# Driver.net
KiCad netlist of a schematic drawn in EAGLE
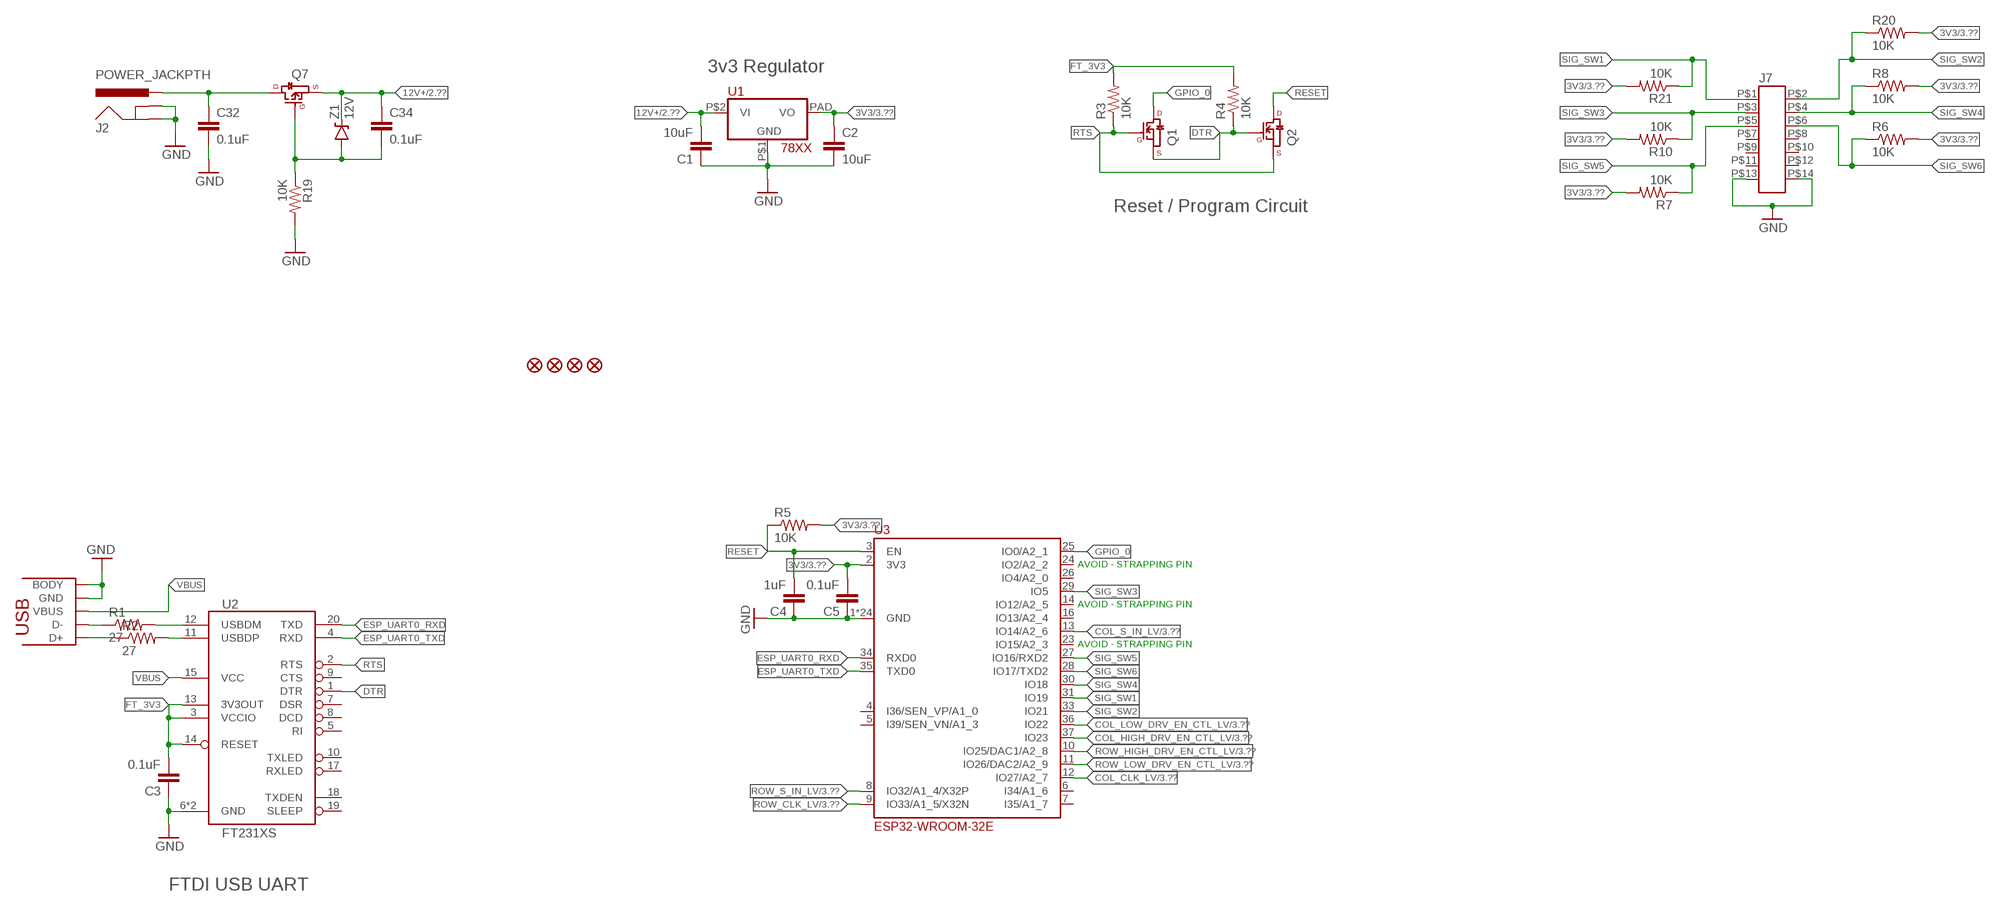
[diagram p0: schematic, sheet 1]
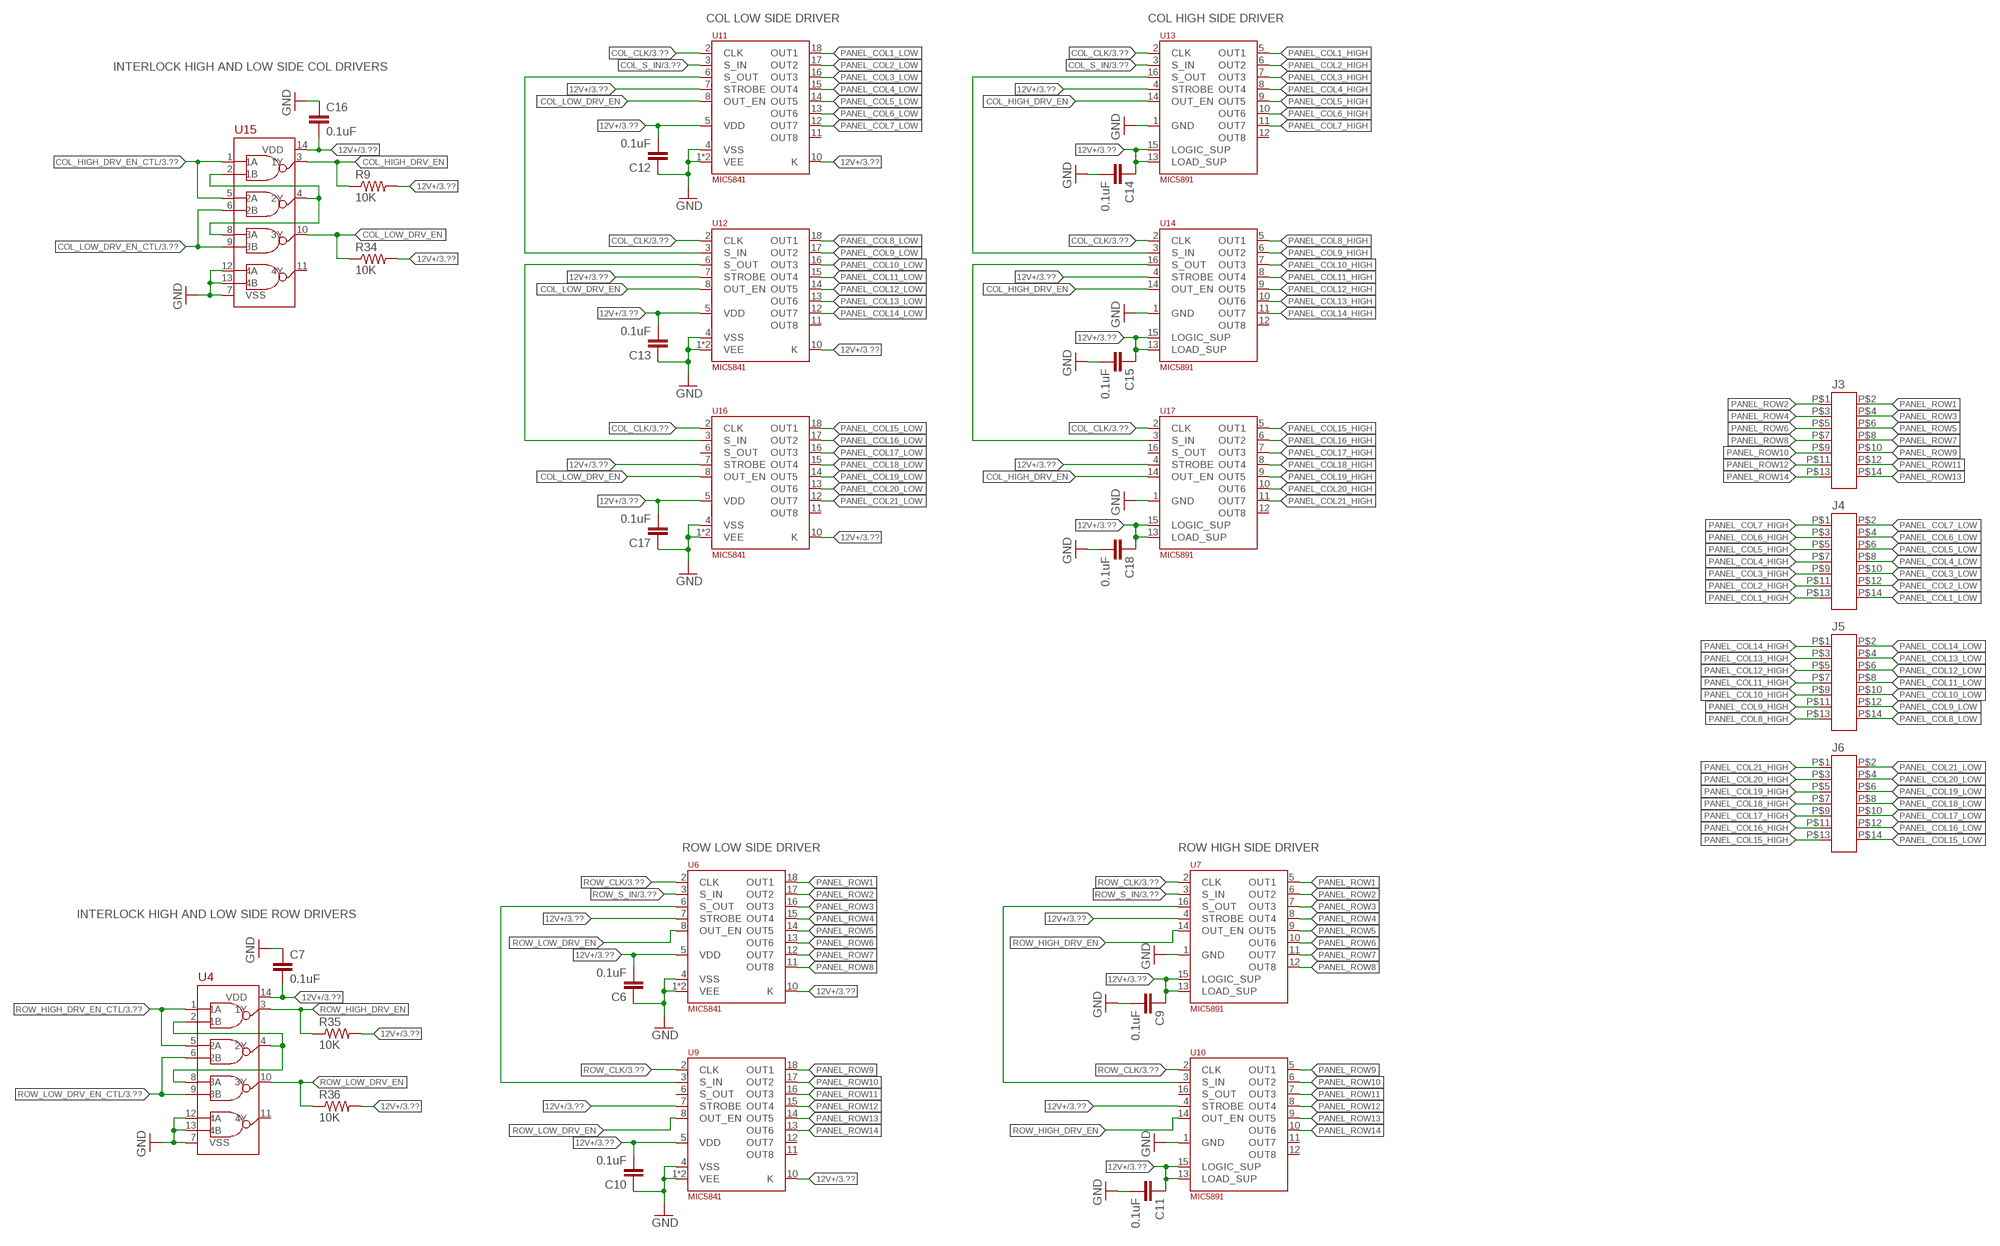
[diagram p1: schematic, sheet 2]
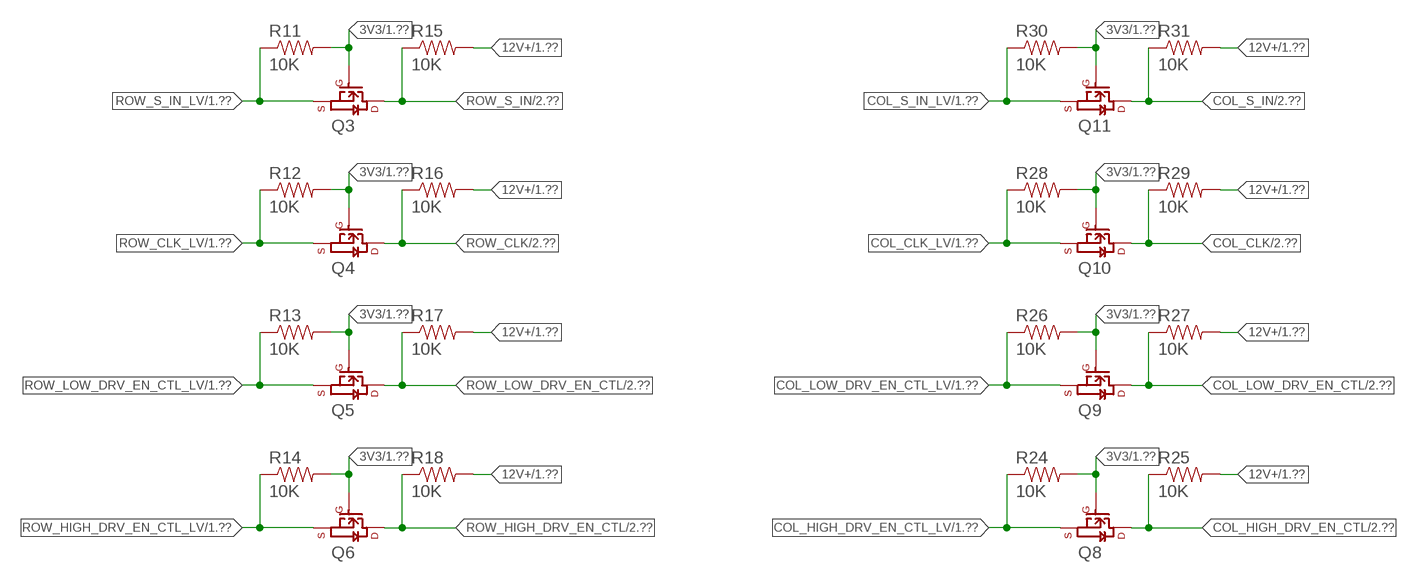
[diagram p2: schematic, sheet 3]

(export (version "E")
  (design (tool "Eeschema 10.0.6"))
  (components
    (comp (ref "Q3")
      (value "MOSFET_N_CHANNELFDV305N")
      (footprint "eagle-import:SOT-23")
      (libsource (lib "eagle-import") (part "MOSFET_N_CHANNELFDV305N"))
    )
    (comp (ref "Q4")
      (value "MOSFET_N_CHANNELFDV305N")
      (footprint "eagle-import:SOT-23")
      (libsource (lib "eagle-import") (part "MOSFET_N_CHANNELFDV305N"))
    )
    (comp (ref "Q5")
      (value "MOSFET_N_CHANNELFDV305N")
      (footprint "eagle-import:SOT-23")
      (libsource (lib "eagle-import") (part "MOSFET_N_CHANNELFDV305N"))
    )
    (comp (ref "Q6")
      (value "MOSFET_N_CHANNELFDV305N")
      (footprint "eagle-import:SOT-23")
      (libsource (lib "eagle-import") (part "MOSFET_N_CHANNELFDV305N"))
    )
    (comp (ref "Q8")
      (value "MOSFET_N_CHANNELFDV305N")
      (footprint "eagle-import:SOT-23")
      (libsource (lib "eagle-import") (part "MOSFET_N_CHANNELFDV305N"))
    )
    (comp (ref "Q9")
      (value "MOSFET_N_CHANNELFDV305N")
      (footprint "eagle-import:SOT-23")
      (libsource (lib "eagle-import") (part "MOSFET_N_CHANNELFDV305N"))
    )
    (comp (ref "Q10")
      (value "MOSFET_N_CHANNELFDV305N")
      (footprint "eagle-import:SOT-23")
      (libsource (lib "eagle-import") (part "MOSFET_N_CHANNELFDV305N"))
    )
    (comp (ref "Q11")
      (value "MOSFET_N_CHANNELFDV305N")
      (footprint "eagle-import:SOT-23")
      (libsource (lib "eagle-import") (part "MOSFET_N_CHANNELFDV305N"))
    )
    (comp (ref "R11")
      (value "10K")
      (footprint "eagle-import:0603-RES")
      (libsource (lib "eagle-import") (part "RESISTOR0603-RES"))
    )
    (comp (ref "R12")
      (value "10K")
      (footprint "eagle-import:0603-RES")
      (libsource (lib "eagle-import") (part "RESISTOR0603-RES"))
    )
    (comp (ref "R13")
      (value "10K")
      (footprint "eagle-import:0603-RES")
      (libsource (lib "eagle-import") (part "RESISTOR0603-RES"))
    )
    (comp (ref "R14")
      (value "10K")
      (footprint "eagle-import:0603-RES")
      (libsource (lib "eagle-import") (part "RESISTOR0603-RES"))
    )
    (comp (ref "R15")
      (value "10K")
      (footprint "eagle-import:0603-RES")
      (libsource (lib "eagle-import") (part "RESISTOR0603-RES"))
    )
    (comp (ref "R16")
      (value "10K")
      (footprint "eagle-import:0603-RES")
      (libsource (lib "eagle-import") (part "RESISTOR0603-RES"))
    )
    (comp (ref "R17")
      (value "10K")
      (footprint "eagle-import:0603-RES")
      (libsource (lib "eagle-import") (part "RESISTOR0603-RES"))
    )
    (comp (ref "R18")
      (value "10K")
      (footprint "eagle-import:0603-RES")
      (libsource (lib "eagle-import") (part "RESISTOR0603-RES"))
    )
    (comp (ref "R24")
      (value "10K")
      (footprint "eagle-import:0603-RES")
      (libsource (lib "eagle-import") (part "RESISTOR0603-RES"))
    )
    (comp (ref "R25")
      (value "10K")
      (footprint "eagle-import:0603-RES")
      (libsource (lib "eagle-import") (part "RESISTOR0603-RES"))
    )
    (comp (ref "R26")
      (value "10K")
      (footprint "eagle-import:0603-RES")
      (libsource (lib "eagle-import") (part "RESISTOR0603-RES"))
    )
    (comp (ref "R27")
      (value "10K")
      (footprint "eagle-import:0603-RES")
      (libsource (lib "eagle-import") (part "RESISTOR0603-RES"))
    )
    (comp (ref "R28")
      (value "10K")
      (footprint "eagle-import:0603-RES")
      (libsource (lib "eagle-import") (part "RESISTOR0603-RES"))
    )
    (comp (ref "R29")
      (value "10K")
      (footprint "eagle-import:0603-RES")
      (libsource (lib "eagle-import") (part "RESISTOR0603-RES"))
    )
    (comp (ref "R30")
      (value "10K")
      (footprint "eagle-import:0603-RES")
      (libsource (lib "eagle-import") (part "RESISTOR0603-RES"))
    )
    (comp (ref "R31")
      (value "10K")
      (footprint "eagle-import:0603-RES")
      (libsource (lib "eagle-import") (part "RESISTOR0603-RES"))
    )
    (comp (ref "C6")
      (value "0.1uF")
      (footprint "eagle-import:0603-CAP")
      (libsource (lib "eagle-import") (part "CAP0603-CAP"))
    )
    (comp (ref "C7")
      (value "0.1uF")
      (footprint "eagle-import:0603-CAP")
      (libsource (lib "eagle-import") (part "CAP0603-CAP"))
    )
    (comp (ref "C9")
      (value "0.1uF")
      (footprint "eagle-import:0603-CAP")
      (libsource (lib "eagle-import") (part "CAP0603-CAP"))
    )
    (comp (ref "C10")
      (value "0.1uF")
      (footprint "eagle-import:0603-CAP")
      (libsource (lib "eagle-import") (part "CAP0603-CAP"))
    )
    (comp (ref "C11")
      (value "0.1uF")
      (footprint "eagle-import:0603-CAP")
      (libsource (lib "eagle-import") (part "CAP0603-CAP"))
    )
    (comp (ref "C12")
      (value "0.1uF")
      (footprint "eagle-import:0603-CAP")
      (libsource (lib "eagle-import") (part "CAP0603-CAP"))
    )
    (comp (ref "C13")
      (value "0.1uF")
      (footprint "eagle-import:0603-CAP")
      (libsource (lib "eagle-import") (part "CAP0603-CAP"))
    )
    (comp (ref "C14")
      (value "0.1uF")
      (footprint "eagle-import:0603-CAP")
      (libsource (lib "eagle-import") (part "CAP0603-CAP"))
    )
    (comp (ref "C15")
      (value "0.1uF")
      (footprint "eagle-import:0603-CAP")
      (libsource (lib "eagle-import") (part "CAP0603-CAP"))
    )
    (comp (ref "C16")
      (value "0.1uF")
      (footprint "eagle-import:0603-CAP")
      (libsource (lib "eagle-import") (part "CAP0603-CAP"))
    )
    (comp (ref "C17")
      (value "0.1uF")
      (footprint "eagle-import:0603-CAP")
      (libsource (lib "eagle-import") (part "CAP0603-CAP"))
    )
    (comp (ref "C18")
      (value "0.1uF")
      (footprint "eagle-import:0603-CAP")
      (libsource (lib "eagle-import") (part "CAP0603-CAP"))
    )
    (comp (ref "J3")
      (value "HEADER-2X7")
      (footprint "eagle-import:3M-3000SERIES-HEADER-RIGHTANGLE")
      (libsource (lib "eagle-import") (part "HEADER-2X7"))
    )
    (comp (ref "J4")
      (value "HEADER-2X7")
      (footprint "eagle-import:3M-3000SERIES-HEADER-RIGHTANGLE")
      (libsource (lib "eagle-import") (part "HEADER-2X7"))
    )
    (comp (ref "J5")
      (value "HEADER-2X7")
      (footprint "eagle-import:3M-3000SERIES-HEADER-RIGHTANGLE")
      (libsource (lib "eagle-import") (part "HEADER-2X7"))
    )
    (comp (ref "J6")
      (value "HEADER-2X7")
      (footprint "eagle-import:3M-3000SERIES-HEADER-RIGHTANGLE")
      (libsource (lib "eagle-import") (part "HEADER-2X7"))
    )
    (comp (ref "R9")
      (value "10K")
      (footprint "eagle-import:0603-RES")
      (libsource (lib "eagle-import") (part "RESISTOR0603-RES"))
    )
    (comp (ref "R34")
      (value "10K")
      (footprint "eagle-import:0603-RES")
      (libsource (lib "eagle-import") (part "RESISTOR0603-RES"))
    )
    (comp (ref "R35")
      (value "10K")
      (footprint "eagle-import:0603-RES")
      (libsource (lib "eagle-import") (part "RESISTOR0603-RES"))
    )
    (comp (ref "R36")
      (value "10K")
      (footprint "eagle-import:0603-RES")
      (libsource (lib "eagle-import") (part "RESISTOR0603-RES"))
    )
    (comp (ref "U4")
      (value "HEF4093B")
      (footprint "eagle-import:SOIC-14")
      (libsource (lib "eagle-import") (part "HEF4093B"))
    )
    (comp (ref "U6")
      (value "MIC5841")
      (footprint "eagle-import:SOIC-18-WIDE")
      (libsource (lib "eagle-import") (part "MIC5841"))
    )
    (comp (ref "U7")
      (value "MIC5891")
      (footprint "eagle-import:SOIC-16-WIDE")
      (libsource (lib "eagle-import") (part "MIC5891"))
    )
    (comp (ref "U9")
      (value "MIC5841")
      (footprint "eagle-import:SOIC-18-WIDE")
      (libsource (lib "eagle-import") (part "MIC5841"))
    )
    (comp (ref "U10")
      (value "MIC5891")
      (footprint "eagle-import:SOIC-16-WIDE")
      (libsource (lib "eagle-import") (part "MIC5891"))
    )
    (comp (ref "U11")
      (value "MIC5841")
      (footprint "eagle-import:SOIC-18-WIDE")
      (libsource (lib "eagle-import") (part "MIC5841"))
    )
    (comp (ref "U12")
      (value "MIC5841")
      (footprint "eagle-import:SOIC-18-WIDE")
      (libsource (lib "eagle-import") (part "MIC5841"))
    )
    (comp (ref "U13")
      (value "MIC5891")
      (footprint "eagle-import:SOIC-16-WIDE")
      (libsource (lib "eagle-import") (part "MIC5891"))
    )
    (comp (ref "U14")
      (value "MIC5891")
      (footprint "eagle-import:SOIC-16-WIDE")
      (libsource (lib "eagle-import") (part "MIC5891"))
    )
    (comp (ref "U15")
      (value "HEF4093B")
      (footprint "eagle-import:SOIC-14")
      (libsource (lib "eagle-import") (part "HEF4093B"))
    )
    (comp (ref "U16")
      (value "MIC5841")
      (footprint "eagle-import:SOIC-18-WIDE")
      (libsource (lib "eagle-import") (part "MIC5841"))
    )
    (comp (ref "U17")
      (value "MIC5891")
      (footprint "eagle-import:SOIC-16-WIDE")
      (libsource (lib "eagle-import") (part "MIC5891"))
    )
    (comp (ref "C1")
      (value "10uF")
      (footprint "eagle-import:1206")
      (libsource (lib "eagle-import") (part "CAP1206"))
    )
    (comp (ref "C2")
      (value "10uF")
      (footprint "eagle-import:1206")
      (libsource (lib "eagle-import") (part "CAP1206"))
    )
    (comp (ref "C3")
      (value "0.1uF")
      (footprint "eagle-import:0603-CAP")
      (libsource (lib "eagle-import") (part "CAP0603-CAP"))
    )
    (comp (ref "C4")
      (value "1uF")
      (footprint "eagle-import:0603-CAP")
      (libsource (lib "eagle-import") (part "CAP0603-CAP"))
    )
    (comp (ref "C5")
      (value "0.1uF")
      (footprint "eagle-import:0603-CAP")
      (libsource (lib "eagle-import") (part "CAP0603-CAP"))
    )
    (comp (ref "C32")
      (value "0.1uF")
      (footprint "eagle-import:0603-CAP")
      (libsource (lib "eagle-import") (part "CAP0603-CAP"))
    )
    (comp (ref "C34")
      (value "0.1uF")
      (footprint "eagle-import:0603-CAP")
      (libsource (lib "eagle-import") (part "CAP0603-CAP"))
    )
    (comp (ref "FID1")
      (value "FIDUCIAL")
      (footprint "eagle-import:FIDUCIAL")
      (libsource (lib "eagle-import") (part "FIDUCIAL"))
    )
    (comp (ref "FID2")
      (value "FIDUCIAL")
      (footprint "eagle-import:FIDUCIAL")
      (libsource (lib "eagle-import") (part "FIDUCIAL"))
    )
    (comp (ref "FID3")
      (value "FIDUCIAL")
      (footprint "eagle-import:FIDUCIAL")
      (libsource (lib "eagle-import") (part "FIDUCIAL"))
    )
    (comp (ref "FID4")
      (value "FIDUCIAL")
      (footprint "eagle-import:FIDUCIAL")
      (libsource (lib "eagle-import") (part "FIDUCIAL"))
    )
    (comp (ref "J1")
      (value "USB-MICROB")
      (footprint "eagle-import:USB-MICROB-10118192")
      (libsource (lib "eagle-import") (part "USB-MICROB"))
    )
    (comp (ref "J2")
      (value "POWER_JACKPTH")
      (footprint "eagle-import:POWER_JACK_PTH")
      (libsource (lib "eagle-import") (part "POWER_JACKPTH"))
    )
    (comp (ref "J7")
      (value "HEADER-2X7")
      (footprint "eagle-import:3M-3000SERIES-HEADER-RIGHTANGLE")
      (libsource (lib "eagle-import") (part "HEADER-2X7"))
    )
    (comp (ref "Q1")
      (value "MOSFET_N_CHANNELFDV305N")
      (footprint "eagle-import:SOT-23")
      (libsource (lib "eagle-import") (part "MOSFET_N_CHANNELFDV305N"))
    )
    (comp (ref "Q2")
      (value "MOSFET_N_CHANNELFDV305N")
      (footprint "eagle-import:SOT-23")
      (libsource (lib "eagle-import") (part "MOSFET_N_CHANNELFDV305N"))
    )
    (comp (ref "Q7")
      (value "MOSFET_P_CHANNELDMP4015SSS")
      (footprint "eagle-import:SO08")
      (libsource (lib "eagle-import") (part "MOSFET_P_CHANNELDMP4015SSS"))
    )
    (comp (ref "R1")
      (value "27")
      (footprint "eagle-import:0603-RES")
      (libsource (lib "eagle-import") (part "RESISTOR0603-RES"))
    )
    (comp (ref "R2")
      (value "27")
      (footprint "eagle-import:0603-RES")
      (libsource (lib "eagle-import") (part "RESISTOR0603-RES"))
    )
    (comp (ref "R3")
      (value "10K")
      (footprint "eagle-import:0603-RES")
      (libsource (lib "eagle-import") (part "RESISTOR0603-RES"))
    )
    (comp (ref "R4")
      (value "10K")
      (footprint "eagle-import:0603-RES")
      (libsource (lib "eagle-import") (part "RESISTOR0603-RES"))
    )
    (comp (ref "R5")
      (value "10K")
      (footprint "eagle-import:0603-RES")
      (libsource (lib "eagle-import") (part "RESISTOR0603-RES"))
    )
    (comp (ref "R6")
      (value "10K")
      (footprint "eagle-import:0603-RES")
      (libsource (lib "eagle-import") (part "RESISTOR0603-RES"))
    )
    (comp (ref "R7")
      (value "10K")
      (footprint "eagle-import:0603-RES")
      (libsource (lib "eagle-import") (part "RESISTOR0603-RES"))
    )
    (comp (ref "R8")
      (value "10K")
      (footprint "eagle-import:0603-RES")
      (libsource (lib "eagle-import") (part "RESISTOR0603-RES"))
    )
    (comp (ref "R10")
      (value "10K")
      (footprint "eagle-import:0603-RES")
      (libsource (lib "eagle-import") (part "RESISTOR0603-RES"))
    )
    (comp (ref "R19")
      (value "10K")
      (footprint "eagle-import:0603-RES")
      (libsource (lib "eagle-import") (part "RESISTOR0603-RES"))
    )
    (comp (ref "R20")
      (value "10K")
      (footprint "eagle-import:0603-RES")
      (libsource (lib "eagle-import") (part "RESISTOR0603-RES"))
    )
    (comp (ref "R21")
      (value "10K")
      (footprint "eagle-import:0603-RES")
      (libsource (lib "eagle-import") (part "RESISTOR0603-RES"))
    )
    (comp (ref "U1")
      (value "7805AZ1117_TO252")
      (footprint "eagle-import:DPAK-3")
      (libsource (lib "eagle-import") (part "7805AZ1117_TO252"))
    )
    (comp (ref "U2")
      (value "FT231XS")
      (footprint "eagle-import:SSOP-20")
      (libsource (lib "eagle-import") (part "FT231XS"))
    )
    (comp (ref "U3")
      (value "ESP32-WROOM-32E")
      (footprint "eagle-import:ESP32-WROOM-32E")
      (libsource (lib "eagle-import") (part "ESP32-WROOM-32E"))
    )
    (comp (ref "Z1")
      (value "12V")
      (footprint "eagle-import:SOT-23")
      (libsource (lib "eagle-import") (part "DIODE-ZENERSOT-23"))
    )
  )
  (nets
    (net (code "1") (name "3V3") (class "Default")
      (node (ref "C2") (pin "1") (pinfunction "1_1") (pintype "passive"))
      (node (ref "C5") (pin "2") (pinfunction "2_2") (pintype "passive"))
      (node (ref "Q10") (pin "1") (pinfunction "G_1") (pintype "bidirectional"))
      (node (ref "Q11") (pin "1") (pinfunction "G_1") (pintype "bidirectional"))
      (node (ref "Q3") (pin "1") (pinfunction "G_1") (pintype "bidirectional"))
      (node (ref "Q4") (pin "1") (pinfunction "G_1") (pintype "bidirectional"))
      (node (ref "Q5") (pin "1") (pinfunction "G_1") (pintype "bidirectional"))
      (node (ref "Q6") (pin "1") (pinfunction "G_1") (pintype "bidirectional"))
      (node (ref "Q8") (pin "1") (pinfunction "G_1") (pintype "bidirectional"))
      (node (ref "Q9") (pin "1") (pinfunction "G_1") (pintype "bidirectional"))
      (node (ref "R10") (pin "2") (pinfunction "2_2") (pintype "passive"))
      (node (ref "R11") (pin "2") (pinfunction "2_2") (pintype "passive"))
      (node (ref "R12") (pin "2") (pinfunction "2_2") (pintype "passive"))
      (node (ref "R13") (pin "2") (pinfunction "2_2") (pintype "passive"))
      (node (ref "R14") (pin "2") (pinfunction "2_2") (pintype "passive"))
      (node (ref "R20") (pin "2") (pinfunction "2_2") (pintype "passive"))
      (node (ref "R21") (pin "2") (pinfunction "2_2") (pintype "passive"))
      (node (ref "R24") (pin "2") (pinfunction "2_2") (pintype "passive"))
      (node (ref "R26") (pin "2") (pinfunction "2_2") (pintype "passive"))
      (node (ref "R28") (pin "2") (pinfunction "2_2") (pintype "passive"))
      (node (ref "R30") (pin "2") (pinfunction "2_2") (pintype "passive"))
      (node (ref "R5") (pin "2") (pinfunction "2_2") (pintype "passive"))
      (node (ref "R6") (pin "2") (pinfunction "2_2") (pintype "passive"))
      (node (ref "R7") (pin "2") (pinfunction "2_2") (pintype "passive"))
      (node (ref "R8") (pin "2") (pinfunction "2_2") (pintype "passive"))
      (node (ref "U1") (pin "PAD") (pinfunction "VO_PAD") (pintype "power_in"))
      (node (ref "U3") (pin "2") (pinfunction "3V3_2") (pintype "power_in"))
    )
    (net (code "2") (name "12V+") (class "Default")
      (node (ref "C1") (pin "2") (pinfunction "2_2") (pintype "passive"))
      (node (ref "C10") (pin "2") (pinfunction "2_2") (pintype "passive"))
      (node (ref "C11") (pin "1") (pinfunction "1_1") (pintype "passive"))
      (node (ref "C12") (pin "2") (pinfunction "2_2") (pintype "passive"))
      (node (ref "C13") (pin "2") (pinfunction "2_2") (pintype "passive"))
      (node (ref "C14") (pin "1") (pinfunction "1_1") (pintype "passive"))
      (node (ref "C15") (pin "1") (pinfunction "1_1") (pintype "passive"))
      (node (ref "C16") (pin "2") (pinfunction "2_2") (pintype "passive"))
      (node (ref "C17") (pin "2") (pinfunction "2_2") (pintype "passive"))
      (node (ref "C18") (pin "1") (pinfunction "1_1") (pintype "passive"))
      (node (ref "C34") (pin "1") (pinfunction "1_1") (pintype "passive"))
      (node (ref "C6") (pin "2") (pinfunction "2_2") (pintype "passive"))
      (node (ref "C7") (pin "2") (pinfunction "2_2") (pintype "passive"))
      (node (ref "C9") (pin "1") (pinfunction "1_1") (pintype "passive"))
      (node (ref "Q7") (pin "1") (pinfunction "S_1") (pintype "bidirectional"))
      (node (ref "Q7") (pin "2") (pinfunction "S_2") (pintype "bidirectional"))
      (node (ref "Q7") (pin "3") (pinfunction "S_3") (pintype "bidirectional"))
      (node (ref "R15") (pin "2") (pinfunction "2_2") (pintype "passive"))
      (node (ref "R16") (pin "2") (pinfunction "2_2") (pintype "passive"))
      (node (ref "R17") (pin "2") (pinfunction "2_2") (pintype "passive"))
      (node (ref "R18") (pin "2") (pinfunction "2_2") (pintype "passive"))
      (node (ref "R25") (pin "2") (pinfunction "2_2") (pintype "passive"))
      (node (ref "R27") (pin "2") (pinfunction "2_2") (pintype "passive"))
      (node (ref "R29") (pin "2") (pinfunction "2_2") (pintype "passive"))
      (node (ref "R31") (pin "2") (pinfunction "2_2") (pintype "passive"))
      (node (ref "R34") (pin "2") (pinfunction "2_2") (pintype "passive"))
      (node (ref "R35") (pin "2") (pinfunction "2_2") (pintype "passive"))
      (node (ref "R36") (pin "2") (pinfunction "2_2") (pintype "passive"))
      (node (ref "R9") (pin "2") (pinfunction "2_2") (pintype "passive"))
      (node (ref "U1") (pin "P$2") (pinfunction "VI_P$2") (pintype "power_in"))
      (node (ref "U10") (pin "13") (pinfunction "LOAD_SUP_13") (pintype "bidirectional"))
      (node (ref "U10") (pin "15") (pinfunction "LOGIC_SUP_15") (pintype "bidirectional"))
      (node (ref "U10") (pin "4") (pinfunction "STROBE_4") (pintype "bidirectional"))
      (node (ref "U11") (pin "10") (pinfunction "K_10") (pintype "bidirectional"))
      (node (ref "U11") (pin "5") (pinfunction "VDD_5") (pintype "bidirectional"))
      (node (ref "U11") (pin "7") (pinfunction "STROBE_7") (pintype "bidirectional"))
      (node (ref "U12") (pin "10") (pinfunction "K_10") (pintype "bidirectional"))
      (node (ref "U12") (pin "5") (pinfunction "VDD_5") (pintype "bidirectional"))
      (node (ref "U12") (pin "7") (pinfunction "STROBE_7") (pintype "bidirectional"))
      (node (ref "U13") (pin "13") (pinfunction "LOAD_SUP_13") (pintype "bidirectional"))
      (node (ref "U13") (pin "15") (pinfunction "LOGIC_SUP_15") (pintype "bidirectional"))
      (node (ref "U13") (pin "4") (pinfunction "STROBE_4") (pintype "bidirectional"))
      (node (ref "U14") (pin "13") (pinfunction "LOAD_SUP_13") (pintype "bidirectional"))
      (node (ref "U14") (pin "15") (pinfunction "LOGIC_SUP_15") (pintype "bidirectional"))
      (node (ref "U14") (pin "4") (pinfunction "STROBE_4") (pintype "bidirectional"))
      (node (ref "U15") (pin "14") (pinfunction "VDD_14") (pintype "bidirectional"))
      (node (ref "U16") (pin "10") (pinfunction "K_10") (pintype "bidirectional"))
      (node (ref "U16") (pin "5") (pinfunction "VDD_5") (pintype "bidirectional"))
      (node (ref "U16") (pin "7") (pinfunction "STROBE_7") (pintype "bidirectional"))
      (node (ref "U17") (pin "13") (pinfunction "LOAD_SUP_13") (pintype "bidirectional"))
      (node (ref "U17") (pin "15") (pinfunction "LOGIC_SUP_15") (pintype "bidirectional"))
      (node (ref "U17") (pin "4") (pinfunction "STROBE_4") (pintype "bidirectional"))
      (node (ref "U4") (pin "14") (pinfunction "VDD_14") (pintype "bidirectional"))
      (node (ref "U6") (pin "10") (pinfunction "K_10") (pintype "bidirectional"))
      (node (ref "U6") (pin "5") (pinfunction "VDD_5") (pintype "bidirectional"))
      (node (ref "U6") (pin "7") (pinfunction "STROBE_7") (pintype "bidirectional"))
      (node (ref "U7") (pin "13") (pinfunction "LOAD_SUP_13") (pintype "bidirectional"))
      (node (ref "U7") (pin "15") (pinfunction "LOGIC_SUP_15") (pintype "bidirectional"))
      (node (ref "U7") (pin "4") (pinfunction "STROBE_4") (pintype "bidirectional"))
      (node (ref "U9") (pin "10") (pinfunction "K_10") (pintype "bidirectional"))
      (node (ref "U9") (pin "5") (pinfunction "VDD_5") (pintype "bidirectional"))
      (node (ref "U9") (pin "7") (pinfunction "STROBE_7") (pintype "bidirectional"))
      (node (ref "Z1") (pin "3") (pinfunction "C_3") (pintype "passive"))
    )
    (net (code "3") (name "COL_CLK") (class "Default")
      (node (ref "Q10") (pin "3") (pinfunction "D_3") (pintype "bidirectional"))
      (node (ref "R29") (pin "1") (pinfunction "1_1") (pintype "passive"))
      (node (ref "U11") (pin "2") (pinfunction "CLK_2") (pintype "bidirectional"))
      (node (ref "U12") (pin "2") (pinfunction "CLK_2") (pintype "bidirectional"))
      (node (ref "U13") (pin "2") (pinfunction "CLK_2") (pintype "bidirectional"))
      (node (ref "U14") (pin "2") (pinfunction "CLK_2") (pintype "bidirectional"))
      (node (ref "U16") (pin "2") (pinfunction "CLK_2") (pintype "bidirectional"))
      (node (ref "U17") (pin "2") (pinfunction "CLK_2") (pintype "bidirectional"))
    )
    (net (code "4") (name "COL_CLK_LV") (class "Default")
      (node (ref "Q10") (pin "2") (pinfunction "S_2") (pintype "bidirectional"))
      (node (ref "R28") (pin "1") (pinfunction "1_1") (pintype "passive"))
      (node (ref "U3") (pin "12") (pinfunction "IO27/A2_7_12") (pintype "bidirectional"))
    )
    (net (code "5") (name "COL_HIGH_DRV_EN") (class "Default")
      (node (ref "R9") (pin "1") (pinfunction "1_1") (pintype "passive"))
      (node (ref "U13") (pin "14") (pinfunction "OUT_EN_14") (pintype "bidirectional"))
      (node (ref "U14") (pin "14") (pinfunction "OUT_EN_14") (pintype "bidirectional"))
      (node (ref "U15") (pin "3") (pinfunction "1Y_3") (pintype "bidirectional"))
      (node (ref "U17") (pin "14") (pinfunction "OUT_EN_14") (pintype "bidirectional"))
    )
    (net (code "6") (name "COL_HIGH_DRV_EN_CTL") (class "Default")
      (node (ref "Q8") (pin "3") (pinfunction "D_3") (pintype "bidirectional"))
      (node (ref "R25") (pin "1") (pinfunction "1_1") (pintype "passive"))
      (node (ref "U15") (pin "1") (pinfunction "1A_1") (pintype "bidirectional"))
      (node (ref "U15") (pin "5") (pinfunction "2A_5") (pintype "bidirectional"))
    )
    (net (code "7") (name "COL_HIGH_DRV_EN_CTL_LV") (class "Default")
      (node (ref "Q8") (pin "2") (pinfunction "S_2") (pintype "bidirectional"))
      (node (ref "R24") (pin "1") (pinfunction "1_1") (pintype "passive"))
      (node (ref "U3") (pin "37") (pinfunction "IO23_37") (pintype "bidirectional"))
    )
    (net (code "8") (name "COL_LOW_DRV_EN") (class "Default")
      (node (ref "R34") (pin "1") (pinfunction "1_1") (pintype "passive"))
      (node (ref "U11") (pin "8") (pinfunction "OUT_EN_8") (pintype "bidirectional"))
      (node (ref "U12") (pin "8") (pinfunction "OUT_EN_8") (pintype "bidirectional"))
      (node (ref "U15") (pin "10") (pinfunction "3Y_10") (pintype "bidirectional"))
      (node (ref "U16") (pin "8") (pinfunction "OUT_EN_8") (pintype "bidirectional"))
    )
    (net (code "9") (name "COL_LOW_DRV_EN_CTL") (class "Default")
      (node (ref "Q9") (pin "3") (pinfunction "D_3") (pintype "bidirectional"))
      (node (ref "R27") (pin "1") (pinfunction "1_1") (pintype "passive"))
      (node (ref "U15") (pin "6") (pinfunction "2B_6") (pintype "bidirectional"))
      (node (ref "U15") (pin "9") (pinfunction "3B_9") (pintype "bidirectional"))
    )
    (net (code "10") (name "COL_LOW_DRV_EN_CTL_LV") (class "Default")
      (node (ref "Q9") (pin "2") (pinfunction "S_2") (pintype "bidirectional"))
      (node (ref "R26") (pin "1") (pinfunction "1_1") (pintype "passive"))
      (node (ref "U3") (pin "36") (pinfunction "IO22_36") (pintype "bidirectional"))
    )
    (net (code "11") (name "COL_S_IN") (class "Default")
      (node (ref "Q11") (pin "3") (pinfunction "D_3") (pintype "bidirectional"))
      (node (ref "R31") (pin "1") (pinfunction "1_1") (pintype "passive"))
      (node (ref "U11") (pin "3") (pinfunction "S_IN_3") (pintype "bidirectional"))
      (node (ref "U13") (pin "3") (pinfunction "S_IN_3") (pintype "bidirectional"))
    )
    (net (code "12") (name "COL_S_IN_LV") (class "Default")
      (node (ref "Q11") (pin "2") (pinfunction "S_2") (pintype "bidirectional"))
      (node (ref "R30") (pin "1") (pinfunction "1_1") (pintype "passive"))
      (node (ref "U3") (pin "13") (pinfunction "IO14/A2_6_13") (pintype "bidirectional"))
    )
    (net (code "13") (name "DTR") (class "Default")
      (node (ref "Q1") (pin "2") (pinfunction "S_2") (pintype "bidirectional"))
      (node (ref "Q2") (pin "1") (pinfunction "G_1") (pintype "bidirectional"))
      (node (ref "R4") (pin "1") (pinfunction "1_1") (pintype "passive"))
      (node (ref "U2") (pin "1") (pinfunction "DTR_1") (pintype "output"))
    )
    (net (code "14") (name "ESP_UART0_RXD") (class "Default")
      (node (ref "U2") (pin "20") (pinfunction "TXD_20") (pintype "output"))
      (node (ref "U3") (pin "34") (pinfunction "RXD0_34") (pintype "bidirectional"))
    )
    (net (code "15") (name "ESP_UART0_TXD") (class "Default")
      (node (ref "U2") (pin "4") (pinfunction "RXD_4") (pintype "input"))
      (node (ref "U3") (pin "35") (pinfunction "TXD0_35") (pintype "bidirectional"))
    )
    (net (code "16") (name "FT_3V3") (class "Default")
      (node (ref "C3") (pin "2") (pinfunction "2_2") (pintype "passive"))
      (node (ref "R3") (pin "2") (pinfunction "2_2") (pintype "passive"))
      (node (ref "R4") (pin "2") (pinfunction "2_2") (pintype "passive"))
      (node (ref "U2") (pin "13") (pinfunction "3V3OUT_13") (pintype "output"))
      (node (ref "U2") (pin "14") (pinfunction "RESET_14") (pintype "input"))
      (node (ref "U2") (pin "3") (pinfunction "VCCIO_3") (pintype "power_in"))
    )
    (net (code "17") (name "GND") (class "Default")
      (node (ref "C1") (pin "1") (pinfunction "1_1") (pintype "passive"))
      (node (ref "C10") (pin "1") (pinfunction "1_1") (pintype "passive"))
      (node (ref "C11") (pin "2") (pinfunction "2_2") (pintype "passive"))
      (node (ref "C12") (pin "1") (pinfunction "1_1") (pintype "passive"))
      (node (ref "C13") (pin "1") (pinfunction "1_1") (pintype "passive"))
      (node (ref "C14") (pin "2") (pinfunction "2_2") (pintype "passive"))
      (node (ref "C15") (pin "2") (pinfunction "2_2") (pintype "passive"))
      (node (ref "C16") (pin "1") (pinfunction "1_1") (pintype "passive"))
      (node (ref "C17") (pin "1") (pinfunction "1_1") (pintype "passive"))
      (node (ref "C18") (pin "2") (pinfunction "2_2") (pintype "passive"))
      (node (ref "C2") (pin "2") (pinfunction "2_2") (pintype "passive"))
      (node (ref "C3") (pin "1") (pinfunction "1_1") (pintype "passive"))
      (node (ref "C32") (pin "2") (pinfunction "2_2") (pintype "passive"))
      (node (ref "C4") (pin "1") (pinfunction "1_1") (pintype "passive"))
      (node (ref "C5") (pin "1") (pinfunction "1_1") (pintype "passive"))
      (node (ref "C6") (pin "1") (pinfunction "1_1") (pintype "passive"))
      (node (ref "C7") (pin "1") (pinfunction "1_1") (pintype "passive"))
      (node (ref "C9") (pin "2") (pinfunction "2_2") (pintype "passive"))
      (node (ref "J1") (pin "5") (pinfunction "GND_5") (pintype "bidirectional"))
      (node (ref "J1") (pin "BODY@1") (pinfunction "BODY_BODY@1") (pintype "bidirectional"))
      (node (ref "J1") (pin "BODY@2") (pinfunction "BODY_BODY@2") (pintype "bidirectional"))
      (node (ref "J1") (pin "BODY@3") (pinfunction "BODY_BODY@3") (pintype "bidirectional"))
      (node (ref "J1") (pin "BODY@4") (pinfunction "BODY_BODY@4") (pintype "bidirectional"))
      (node (ref "J1") (pin "BODY@5") (pinfunction "BODY_BODY@5") (pintype "bidirectional"))
      (node (ref "J1") (pin "BODY@6") (pinfunction "BODY_BODY@6") (pintype "bidirectional"))
      (node (ref "J2") (pin "GND") (pinfunction "GND_GND") (pintype "bidirectional"))
      (node (ref "J2") (pin "GNDBREAK") (pinfunction "GNDBREAK_GNDBREAK") (pintype "bidirectional"))
      (node (ref "J7") (pin "P$13") (pinfunction "13_P$13") (pintype "bidirectional"))
      (node (ref "J7") (pin "P$14") (pinfunction "14_P$14") (pintype "bidirectional"))
      (node (ref "R19") (pin "2") (pinfunction "2_2") (pintype "passive"))
      (node (ref "U1") (pin "P$1") (pinfunction "GND_P$1") (pintype "power_in"))
      (node (ref "U10") (pin "1") (pinfunction "GND_1") (pintype "bidirectional"))
      (node (ref "U11") (pin "1") (pinfunction "VEE_1") (pintype "bidirectional"))
      (node (ref "U11") (pin "4") (pinfunction "VSS_4") (pintype "bidirectional"))
      (node (ref "U11") (pin "9") (pinfunction "VEE_9") (pintype "bidirectional"))
      (node (ref "U12") (pin "1") (pinfunction "VEE_1") (pintype "bidirectional"))
      (node (ref "U12") (pin "4") (pinfunction "VSS_4") (pintype "bidirectional"))
      (node (ref "U12") (pin "9") (pinfunction "VEE_9") (pintype "bidirectional"))
      (node (ref "U13") (pin "1") (pinfunction "GND_1") (pintype "bidirectional"))
      (node (ref "U14") (pin "1") (pinfunction "GND_1") (pintype "bidirectional"))
      (node (ref "U15") (pin "12") (pinfunction "4A_12") (pintype "bidirectional"))
      (node (ref "U15") (pin "13") (pinfunction "4B_13") (pintype "bidirectional"))
      (node (ref "U15") (pin "7") (pinfunction "VSS_7") (pintype "bidirectional"))
      (node (ref "U16") (pin "1") (pinfunction "VEE_1") (pintype "bidirectional"))
      (node (ref "U16") (pin "4") (pinfunction "VSS_4") (pintype "bidirectional"))
      (node (ref "U16") (pin "9") (pinfunction "VEE_9") (pintype "bidirectional"))
      (node (ref "U17") (pin "1") (pinfunction "GND_1") (pintype "bidirectional"))
      (node (ref "U2") (pin "16") (pinfunction "GND_16") (pintype "power_in"))
      (node (ref "U2") (pin "6") (pinfunction "GND_6") (pintype "power_in"))
      (node (ref "U3") (pin "1") (pinfunction "GND_1") (pintype "power_in"))
      (node (ref "U3") (pin "15") (pinfunction "GND_15") (pintype "power_in"))
      (node (ref "U3") (pin "38") (pinfunction "GND_38") (pintype "power_in"))
      (node (ref "U3") (pin "P$1") (pinfunction "GND_P$1") (pintype "power_in"))
      (node (ref "U3") (pin "P$10") (pinfunction "GND_P$10") (pintype "power_in"))
      (node (ref "U3") (pin "P$11") (pinfunction "GND_P$11") (pintype "power_in"))
      (node (ref "U3") (pin "P$12") (pinfunction "GND_P$12") (pintype "power_in"))
      (node (ref "U3") (pin "P$2") (pinfunction "GND_P$2") (pintype "power_in"))
      (node (ref "U3") (pin "P$3") (pinfunction "GND_P$3") (pintype "power_in"))
      (node (ref "U3") (pin "P$4") (pinfunction "GND_P$4") (pintype "power_in"))
      (node (ref "U3") (pin "P$5") (pinfunction "GND_P$5") (pintype "power_in"))
      (node (ref "U3") (pin "P$6") (pinfunction "GND_P$6") (pintype "power_in"))
      (node (ref "U3") (pin "P$7") (pinfunction "GND_P$7") (pintype "power_in"))
      (node (ref "U3") (pin "P$8") (pinfunction "GND_P$8") (pintype "power_in"))
      (node (ref "U3") (pin "P$9") (pinfunction "GND_P$9") (pintype "power_in"))
      (node (ref "U3") (pin "PAD@1") (pinfunction "GND_PAD@1") (pintype "power_in"))
      (node (ref "U3") (pin "PAD@2") (pinfunction "GND_PAD@2") (pintype "power_in"))
      (node (ref "U3") (pin "PAD@3") (pinfunction "GND_PAD@3") (pintype "power_in"))
      (node (ref "U3") (pin "PAD@4") (pinfunction "GND_PAD@4") (pintype "power_in"))
      (node (ref "U3") (pin "PAD@5") (pinfunction "GND_PAD@5") (pintype "power_in"))
      (node (ref "U3") (pin "PAD@6") (pinfunction "GND_PAD@6") (pintype "power_in"))
      (node (ref "U3") (pin "PAD@7") (pinfunction "GND_PAD@7") (pintype "power_in"))
      (node (ref "U3") (pin "PAD@8") (pinfunction "GND_PAD@8") (pintype "power_in"))
      (node (ref "U3") (pin "PAD@9") (pinfunction "GND_PAD@9") (pintype "power_in"))
      (node (ref "U4") (pin "12") (pinfunction "4A_12") (pintype "bidirectional"))
      (node (ref "U4") (pin "13") (pinfunction "4B_13") (pintype "bidirectional"))
      (node (ref "U4") (pin "7") (pinfunction "VSS_7") (pintype "bidirectional"))
      (node (ref "U6") (pin "1") (pinfunction "VEE_1") (pintype "bidirectional"))
      (node (ref "U6") (pin "4") (pinfunction "VSS_4") (pintype "bidirectional"))
      (node (ref "U6") (pin "9") (pinfunction "VEE_9") (pintype "bidirectional"))
      (node (ref "U7") (pin "1") (pinfunction "GND_1") (pintype "bidirectional"))
      (node (ref "U9") (pin "1") (pinfunction "VEE_1") (pintype "bidirectional"))
      (node (ref "U9") (pin "4") (pinfunction "VSS_4") (pintype "bidirectional"))
      (node (ref "U9") (pin "9") (pinfunction "VEE_9") (pintype "bidirectional"))
    )
    (net (code "18") (name "GPIO_0") (class "Default")
      (node (ref "Q1") (pin "3") (pinfunction "D_3") (pintype "bidirectional"))
      (node (ref "U3") (pin "25") (pinfunction "IO0/A2_1_25") (pintype "bidirectional"))
    )
    (net (code "19") (name "Net-(C32-Pad1)") (class "Default")
      (node (ref "C32") (pin "1") (pinfunction "1_1") (pintype "passive"))
      (node (ref "J2") (pin "PWR") (pinfunction "PWR_PWR") (pintype "bidirectional"))
      (node (ref "Q7") (pin "5") (pinfunction "D_5") (pintype "bidirectional"))
      (node (ref "Q7") (pin "6") (pinfunction "D_6") (pintype "bidirectional"))
      (node (ref "Q7") (pin "7") (pinfunction "D_7") (pintype "bidirectional"))
      (node (ref "Q7") (pin "8") (pinfunction "D_8") (pintype "bidirectional"))
    )
    (net (code "20") (name "Net-(J1-D+)") (class "Default")
      (node (ref "J1") (pin "3") (pinfunction "D+_3") (pintype "bidirectional"))
      (node (ref "R2") (pin "1") (pinfunction "1_1") (pintype "passive"))
    )
    (net (code "21") (name "Net-(J1-D-)") (class "Default")
      (node (ref "J1") (pin "2") (pinfunction "D-_2") (pintype "bidirectional"))
      (node (ref "R1") (pin "1") (pinfunction "1_1") (pintype "passive"))
    )
    (net (code "22") (name "Net-(Q7-G)") (class "Default")
      (node (ref "C34") (pin "2") (pinfunction "2_2") (pintype "passive"))
      (node (ref "Q7") (pin "4") (pinfunction "G_4") (pintype "bidirectional"))
      (node (ref "R19") (pin "1") (pinfunction "1_1") (pintype "passive"))
      (node (ref "Z1") (pin "1") (pinfunction "A_1") (pintype "passive"))
    )
    (net (code "23") (name "Net-(U2-USBDM)") (class "Default")
      (node (ref "R1") (pin "2") (pinfunction "2_2") (pintype "passive"))
      (node (ref "U2") (pin "12") (pinfunction "USBDM_12") (pintype "bidirectional"))
    )
    (net (code "24") (name "Net-(U2-USBDP)") (class "Default")
      (node (ref "R2") (pin "2") (pinfunction "2_2") (pintype "passive"))
      (node (ref "U2") (pin "11") (pinfunction "USBDP_11") (pintype "bidirectional"))
    )
    (net (code "25") (name "Net-(U4-1B)") (class "Default")
      (node (ref "U4") (pin "2") (pinfunction "1B_2") (pintype "bidirectional"))
      (node (ref "U4") (pin "4") (pinfunction "2Y_4") (pintype "bidirectional"))
      (node (ref "U4") (pin "8") (pinfunction "3A_8") (pintype "bidirectional"))
    )
    (net (code "26") (name "Net-(U6-S_OUT)") (class "Default")
      (node (ref "U6") (pin "6") (pinfunction "S_OUT_6") (pintype "bidirectional"))
      (node (ref "U9") (pin "3") (pinfunction "S_IN_3") (pintype "bidirectional"))
    )
    (net (code "27") (name "Net-(U10-S_IN)") (class "Default")
      (node (ref "U10") (pin "3") (pinfunction "S_IN_3") (pintype "bidirectional"))
      (node (ref "U7") (pin "16") (pinfunction "S_OUT_16") (pintype "bidirectional"))
    )
    (net (code "28") (name "Net-(U11-S_OUT)") (class "Default")
      (node (ref "U11") (pin "6") (pinfunction "S_OUT_6") (pintype "bidirectional"))
      (node (ref "U12") (pin "3") (pinfunction "S_IN_3") (pintype "bidirectional"))
    )
    (net (code "29") (name "Net-(U12-S_OUT)") (class "Default")
      (node (ref "U12") (pin "6") (pinfunction "S_OUT_6") (pintype "bidirectional"))
      (node (ref "U16") (pin "3") (pinfunction "S_IN_3") (pintype "bidirectional"))
    )
    (net (code "30") (name "Net-(U13-S_OUT)") (class "Default")
      (node (ref "U13") (pin "16") (pinfunction "S_OUT_16") (pintype "bidirectional"))
      (node (ref "U14") (pin "3") (pinfunction "S_IN_3") (pintype "bidirectional"))
    )
    (net (code "31") (name "Net-(U14-S_OUT)") (class "Default")
      (node (ref "U14") (pin "16") (pinfunction "S_OUT_16") (pintype "bidirectional"))
      (node (ref "U17") (pin "3") (pinfunction "S_IN_3") (pintype "bidirectional"))
    )
    (net (code "32") (name "Net-(U15-1B)") (class "Default")
      (node (ref "U15") (pin "2") (pinfunction "1B_2") (pintype "bidirectional"))
      (node (ref "U15") (pin "4") (pinfunction "2Y_4") (pintype "bidirectional"))
      (node (ref "U15") (pin "8") (pinfunction "3A_8") (pintype "bidirectional"))
    )
    (net (code "33") (name "PANEL_COL1_HIGH") (class "Default")
      (node (ref "J4") (pin "P$13") (pinfunction "13_P$13") (pintype "bidirectional"))
      (node (ref "U13") (pin "5") (pinfunction "OUT1_5") (pintype "bidirectional"))
    )
    (net (code "34") (name "PANEL_COL1_LOW") (class "Default")
      (node (ref "J4") (pin "P$14") (pinfunction "14_P$14") (pintype "bidirectional"))
      (node (ref "U11") (pin "18") (pinfunction "OUT1_18") (pintype "bidirectional"))
    )
    (net (code "35") (name "PANEL_COL2_HIGH") (class "Default")
      (node (ref "J4") (pin "P$11") (pinfunction "11_P$11") (pintype "bidirectional"))
      (node (ref "U13") (pin "6") (pinfunction "OUT2_6") (pintype "bidirectional"))
    )
    (net (code "36") (name "PANEL_COL2_LOW") (class "Default")
      (node (ref "J4") (pin "P$12") (pinfunction "12_P$12") (pintype "bidirectional"))
      (node (ref "U11") (pin "17") (pinfunction "OUT2_17") (pintype "bidirectional"))
    )
    (net (code "37") (name "PANEL_COL3_HIGH") (class "Default")
      (node (ref "J4") (pin "P$9") (pinfunction "9_P$9") (pintype "bidirectional"))
      (node (ref "U13") (pin "7") (pinfunction "OUT3_7") (pintype "bidirectional"))
    )
    (net (code "38") (name "PANEL_COL3_LOW") (class "Default")
      (node (ref "J4") (pin "P$10") (pinfunction "10_P$10") (pintype "bidirectional"))
      (node (ref "U11") (pin "16") (pinfunction "OUT3_16") (pintype "bidirectional"))
    )
    (net (code "39") (name "PANEL_COL4_HIGH") (class "Default")
      (node (ref "J4") (pin "P$7") (pinfunction "7_P$7") (pintype "bidirectional"))
      (node (ref "U13") (pin "8") (pinfunction "OUT4_8") (pintype "bidirectional"))
    )
    (net (code "40") (name "PANEL_COL4_LOW") (class "Default")
      (node (ref "J4") (pin "P$8") (pinfunction "8_P$8") (pintype "bidirectional"))
      (node (ref "U11") (pin "15") (pinfunction "OUT4_15") (pintype "bidirectional"))
    )
    (net (code "41") (name "PANEL_COL5_HIGH") (class "Default")
      (node (ref "J4") (pin "P$5") (pinfunction "5_P$5") (pintype "bidirectional"))
      (node (ref "U13") (pin "9") (pinfunction "OUT5_9") (pintype "bidirectional"))
    )
    (net (code "42") (name "PANEL_COL5_LOW") (class "Default")
      (node (ref "J4") (pin "P$6") (pinfunction "6_P$6") (pintype "bidirectional"))
      (node (ref "U11") (pin "14") (pinfunction "OUT5_14") (pintype "bidirectional"))
    )
    (net (code "43") (name "PANEL_COL6_HIGH") (class "Default")
      (node (ref "J4") (pin "P$3") (pinfunction "3_P$3") (pintype "bidirectional"))
      (node (ref "U13") (pin "10") (pinfunction "OUT6_10") (pintype "bidirectional"))
    )
    (net (code "44") (name "PANEL_COL6_LOW") (class "Default")
      (node (ref "J4") (pin "P$4") (pinfunction "4_P$4") (pintype "bidirectional"))
      (node (ref "U11") (pin "13") (pinfunction "OUT6_13") (pintype "bidirectional"))
    )
    (net (code "45") (name "PANEL_COL7_HIGH") (class "Default")
      (node (ref "J4") (pin "P$1") (pinfunction "1_P$1") (pintype "bidirectional"))
      (node (ref "U13") (pin "11") (pinfunction "OUT7_11") (pintype "bidirectional"))
    )
    (net (code "46") (name "PANEL_COL7_LOW") (class "Default")
      (node (ref "J4") (pin "P$2") (pinfunction "2_P$2") (pintype "bidirectional"))
      (node (ref "U11") (pin "12") (pinfunction "OUT7_12") (pintype "bidirectional"))
    )
    (net (code "47") (name "PANEL_COL8_HIGH") (class "Default")
      (node (ref "J5") (pin "P$13") (pinfunction "13_P$13") (pintype "bidirectional"))
      (node (ref "U14") (pin "5") (pinfunction "OUT1_5") (pintype "bidirectional"))
    )
    (net (code "48") (name "PANEL_COL8_LOW") (class "Default")
      (node (ref "J5") (pin "P$14") (pinfunction "14_P$14") (pintype "bidirectional"))
      (node (ref "U12") (pin "18") (pinfunction "OUT1_18") (pintype "bidirectional"))
    )
    (net (code "49") (name "PANEL_COL9_HIGH") (class "Default")
      (node (ref "J5") (pin "P$11") (pinfunction "11_P$11") (pintype "bidirectional"))
      (node (ref "U14") (pin "6") (pinfunction "OUT2_6") (pintype "bidirectional"))
    )
    (net (code "50") (name "PANEL_COL9_LOW") (class "Default")
      (node (ref "J5") (pin "P$12") (pinfunction "12_P$12") (pintype "bidirectional"))
      (node (ref "U12") (pin "17") (pinfunction "OUT2_17") (pintype "bidirectional"))
    )
    (net (code "51") (name "PANEL_COL10_HIGH") (class "Default")
      (node (ref "J5") (pin "P$9") (pinfunction "9_P$9") (pintype "bidirectional"))
      (node (ref "U14") (pin "7") (pinfunction "OUT3_7") (pintype "bidirectional"))
    )
    (net (code "52") (name "PANEL_COL10_LOW") (class "Default")
      (node (ref "J5") (pin "P$10") (pinfunction "10_P$10") (pintype "bidirectional"))
      (node (ref "U12") (pin "16") (pinfunction "OUT3_16") (pintype "bidirectional"))
    )
    (net (code "53") (name "PANEL_COL11_HIGH") (class "Default")
      (node (ref "J5") (pin "P$7") (pinfunction "7_P$7") (pintype "bidirectional"))
      (node (ref "U14") (pin "8") (pinfunction "OUT4_8") (pintype "bidirectional"))
    )
    (net (code "54") (name "PANEL_COL11_LOW") (class "Default")
      (node (ref "J5") (pin "P$8") (pinfunction "8_P$8") (pintype "bidirectional"))
      (node (ref "U12") (pin "15") (pinfunction "OUT4_15") (pintype "bidirectional"))
    )
    (net (code "55") (name "PANEL_COL12_HIGH") (class "Default")
      (node (ref "J5") (pin "P$5") (pinfunction "5_P$5") (pintype "bidirectional"))
      (node (ref "U14") (pin "9") (pinfunction "OUT5_9") (pintype "bidirectional"))
    )
    (net (code "56") (name "PANEL_COL12_LOW") (class "Default")
      (node (ref "J5") (pin "P$6") (pinfunction "6_P$6") (pintype "bidirectional"))
      (node (ref "U12") (pin "14") (pinfunction "OUT5_14") (pintype "bidirectional"))
    )
    (net (code "57") (name "PANEL_COL13_HIGH") (class "Default")
      (node (ref "J5") (pin "P$3") (pinfunction "3_P$3") (pintype "bidirectional"))
      (node (ref "U14") (pin "10") (pinfunction "OUT6_10") (pintype "bidirectional"))
    )
    (net (code "58") (name "PANEL_COL13_LOW") (class "Default")
      (node (ref "J5") (pin "P$4") (pinfunction "4_P$4") (pintype "bidirectional"))
      (node (ref "U12") (pin "13") (pinfunction "OUT6_13") (pintype "bidirectional"))
    )
    (net (code "59") (name "PANEL_COL14_HIGH") (class "Default")
      (node (ref "J5") (pin "P$1") (pinfunction "1_P$1") (pintype "bidirectional"))
      (node (ref "U14") (pin "11") (pinfunction "OUT7_11") (pintype "bidirectional"))
    )
    (net (code "60") (name "PANEL_COL14_LOW") (class "Default")
      (node (ref "J5") (pin "P$2") (pinfunction "2_P$2") (pintype "bidirectional"))
      (node (ref "U12") (pin "12") (pinfunction "OUT7_12") (pintype "bidirectional"))
    )
    (net (code "61") (name "PANEL_COL15_HIGH") (class "Default")
      (node (ref "J6") (pin "P$13") (pinfunction "13_P$13") (pintype "bidirectional"))
      (node (ref "U17") (pin "5") (pinfunction "OUT1_5") (pintype "bidirectional"))
    )
    (net (code "62") (name "PANEL_COL15_LOW") (class "Default")
      (node (ref "J6") (pin "P$14") (pinfunction "14_P$14") (pintype "bidirectional"))
      (node (ref "U16") (pin "18") (pinfunction "OUT1_18") (pintype "bidirectional"))
    )
    (net (code "63") (name "PANEL_COL16_HIGH") (class "Default")
      (node (ref "J6") (pin "P$11") (pinfunction "11_P$11") (pintype "bidirectional"))
      (node (ref "U17") (pin "6") (pinfunction "OUT2_6") (pintype "bidirectional"))
    )
    (net (code "64") (name "PANEL_COL16_LOW") (class "Default")
      (node (ref "J6") (pin "P$12") (pinfunction "12_P$12") (pintype "bidirectional"))
      (node (ref "U16") (pin "17") (pinfunction "OUT2_17") (pintype "bidirectional"))
    )
    (net (code "65") (name "PANEL_COL17_HIGH") (class "Default")
      (node (ref "J6") (pin "P$9") (pinfunction "9_P$9") (pintype "bidirectional"))
      (node (ref "U17") (pin "7") (pinfunction "OUT3_7") (pintype "bidirectional"))
    )
    (net (code "66") (name "PANEL_COL17_LOW") (class "Default")
      (node (ref "J6") (pin "P$10") (pinfunction "10_P$10") (pintype "bidirectional"))
      (node (ref "U16") (pin "16") (pinfunction "OUT3_16") (pintype "bidirectional"))
    )
    (net (code "67") (name "PANEL_COL18_HIGH") (class "Default")
      (node (ref "J6") (pin "P$7") (pinfunction "7_P$7") (pintype "bidirectional"))
      (node (ref "U17") (pin "8") (pinfunction "OUT4_8") (pintype "bidirectional"))
    )
    (net (code "68") (name "PANEL_COL18_LOW") (class "Default")
      (node (ref "J6") (pin "P$8") (pinfunction "8_P$8") (pintype "bidirectional"))
      (node (ref "U16") (pin "15") (pinfunction "OUT4_15") (pintype "bidirectional"))
    )
    (net (code "69") (name "PANEL_COL19_HIGH") (class "Default")
      (node (ref "J6") (pin "P$5") (pinfunction "5_P$5") (pintype "bidirectional"))
      (node (ref "U17") (pin "9") (pinfunction "OUT5_9") (pintype "bidirectional"))
    )
    (net (code "70") (name "PANEL_COL19_LOW") (class "Default")
      (node (ref "J6") (pin "P$6") (pinfunction "6_P$6") (pintype "bidirectional"))
      (node (ref "U16") (pin "14") (pinfunction "OUT5_14") (pintype "bidirectional"))
    )
    (net (code "71") (name "PANEL_COL20_HIGH") (class "Default")
      (node (ref "J6") (pin "P$3") (pinfunction "3_P$3") (pintype "bidirectional"))
      (node (ref "U17") (pin "10") (pinfunction "OUT6_10") (pintype "bidirectional"))
    )
    (net (code "72") (name "PANEL_COL20_LOW") (class "Default")
      (node (ref "J6") (pin "P$4") (pinfunction "4_P$4") (pintype "bidirectional"))
      (node (ref "U16") (pin "13") (pinfunction "OUT6_13") (pintype "bidirectional"))
    )
    (net (code "73") (name "PANEL_COL21_HIGH") (class "Default")
      (node (ref "J6") (pin "P$1") (pinfunction "1_P$1") (pintype "bidirectional"))
      (node (ref "U17") (pin "11") (pinfunction "OUT7_11") (pintype "bidirectional"))
    )
    (net (code "74") (name "PANEL_COL21_LOW") (class "Default")
      (node (ref "J6") (pin "P$2") (pinfunction "2_P$2") (pintype "bidirectional"))
      (node (ref "U16") (pin "12") (pinfunction "OUT7_12") (pintype "bidirectional"))
    )
    (net (code "75") (name "PANEL_ROW1") (class "Default")
      (node (ref "J3") (pin "P$2") (pinfunction "2_P$2") (pintype "bidirectional"))
      (node (ref "U6") (pin "18") (pinfunction "OUT1_18") (pintype "bidirectional"))
      (node (ref "U7") (pin "5") (pinfunction "OUT1_5") (pintype "bidirectional"))
    )
    (net (code "76") (name "PANEL_ROW2") (class "Default")
      (node (ref "J3") (pin "P$1") (pinfunction "1_P$1") (pintype "bidirectional"))
      (node (ref "U6") (pin "17") (pinfunction "OUT2_17") (pintype "bidirectional"))
      (node (ref "U7") (pin "6") (pinfunction "OUT2_6") (pintype "bidirectional"))
    )
    (net (code "77") (name "PANEL_ROW3") (class "Default")
      (node (ref "J3") (pin "P$4") (pinfunction "4_P$4") (pintype "bidirectional"))
      (node (ref "U6") (pin "16") (pinfunction "OUT3_16") (pintype "bidirectional"))
      (node (ref "U7") (pin "7") (pinfunction "OUT3_7") (pintype "bidirectional"))
    )
    (net (code "78") (name "PANEL_ROW4") (class "Default")
      (node (ref "J3") (pin "P$3") (pinfunction "3_P$3") (pintype "bidirectional"))
      (node (ref "U6") (pin "15") (pinfunction "OUT4_15") (pintype "bidirectional"))
      (node (ref "U7") (pin "8") (pinfunction "OUT4_8") (pintype "bidirectional"))
    )
    (net (code "79") (name "PANEL_ROW5") (class "Default")
      (node (ref "J3") (pin "P$6") (pinfunction "6_P$6") (pintype "bidirectional"))
      (node (ref "U6") (pin "14") (pinfunction "OUT5_14") (pintype "bidirectional"))
      (node (ref "U7") (pin "9") (pinfunction "OUT5_9") (pintype "bidirectional"))
    )
    (net (code "80") (name "PANEL_ROW6") (class "Default")
      (node (ref "J3") (pin "P$5") (pinfunction "5_P$5") (pintype "bidirectional"))
      (node (ref "U6") (pin "13") (pinfunction "OUT6_13") (pintype "bidirectional"))
      (node (ref "U7") (pin "10") (pinfunction "OUT6_10") (pintype "bidirectional"))
    )
    (net (code "81") (name "PANEL_ROW7") (class "Default")
      (node (ref "J3") (pin "P$8") (pinfunction "8_P$8") (pintype "bidirectional"))
      (node (ref "U6") (pin "12") (pinfunction "OUT7_12") (pintype "bidirectional"))
      (node (ref "U7") (pin "11") (pinfunction "OUT7_11") (pintype "bidirectional"))
    )
    (net (code "82") (name "PANEL_ROW8") (class "Default")
      (node (ref "J3") (pin "P$7") (pinfunction "7_P$7") (pintype "bidirectional"))
      (node (ref "U6") (pin "11") (pinfunction "OUT8_11") (pintype "bidirectional"))
      (node (ref "U7") (pin "12") (pinfunction "OUT8_12") (pintype "bidirectional"))
    )
    (net (code "83") (name "PANEL_ROW9") (class "Default")
      (node (ref "J3") (pin "P$10") (pinfunction "10_P$10") (pintype "bidirectional"))
      (node (ref "U10") (pin "5") (pinfunction "OUT1_5") (pintype "bidirectional"))
      (node (ref "U9") (pin "18") (pinfunction "OUT1_18") (pintype "bidirectional"))
    )
    (net (code "84") (name "PANEL_ROW10") (class "Default")
      (node (ref "J3") (pin "P$9") (pinfunction "9_P$9") (pintype "bidirectional"))
      (node (ref "U10") (pin "6") (pinfunction "OUT2_6") (pintype "bidirectional"))
      (node (ref "U9") (pin "17") (pinfunction "OUT2_17") (pintype "bidirectional"))
    )
    (net (code "85") (name "PANEL_ROW11") (class "Default")
      (node (ref "J3") (pin "P$12") (pinfunction "12_P$12") (pintype "bidirectional"))
      (node (ref "U10") (pin "7") (pinfunction "OUT3_7") (pintype "bidirectional"))
      (node (ref "U9") (pin "16") (pinfunction "OUT3_16") (pintype "bidirectional"))
    )
    (net (code "86") (name "PANEL_ROW12") (class "Default")
      (node (ref "J3") (pin "P$11") (pinfunction "11_P$11") (pintype "bidirectional"))
      (node (ref "U10") (pin "8") (pinfunction "OUT4_8") (pintype "bidirectional"))
      (node (ref "U9") (pin "15") (pinfunction "OUT4_15") (pintype "bidirectional"))
    )
    (net (code "87") (name "PANEL_ROW13") (class "Default")
      (node (ref "J3") (pin "P$14") (pinfunction "14_P$14") (pintype "bidirectional"))
      (node (ref "U10") (pin "9") (pinfunction "OUT5_9") (pintype "bidirectional"))
      (node (ref "U9") (pin "14") (pinfunction "OUT5_14") (pintype "bidirectional"))
    )
    (net (code "88") (name "PANEL_ROW14") (class "Default")
      (node (ref "J3") (pin "P$13") (pinfunction "13_P$13") (pintype "bidirectional"))
      (node (ref "U10") (pin "10") (pinfunction "OUT6_10") (pintype "bidirectional"))
      (node (ref "U9") (pin "13") (pinfunction "OUT6_13") (pintype "bidirectional"))
    )
    (net (code "89") (name "RESET") (class "Default")
      (node (ref "C4") (pin "2") (pinfunction "2_2") (pintype "passive"))
      (node (ref "Q2") (pin "3") (pinfunction "D_3") (pintype "bidirectional"))
      (node (ref "R5") (pin "1") (pinfunction "1_1") (pintype "passive"))
      (node (ref "U3") (pin "3") (pinfunction "EN_3") (pintype "input"))
    )
    (net (code "90") (name "ROW_CLK") (class "Default")
      (node (ref "Q4") (pin "3") (pinfunction "D_3") (pintype "bidirectional"))
      (node (ref "R16") (pin "1") (pinfunction "1_1") (pintype "passive"))
      (node (ref "U10") (pin "2") (pinfunction "CLK_2") (pintype "bidirectional"))
      (node (ref "U6") (pin "2") (pinfunction "CLK_2") (pintype "bidirectional"))
      (node (ref "U7") (pin "2") (pinfunction "CLK_2") (pintype "bidirectional"))
      (node (ref "U9") (pin "2") (pinfunction "CLK_2") (pintype "bidirectional"))
    )
    (net (code "91") (name "ROW_CLK_LV") (class "Default")
      (node (ref "Q4") (pin "2") (pinfunction "S_2") (pintype "bidirectional"))
      (node (ref "R12") (pin "1") (pinfunction "1_1") (pintype "passive"))
      (node (ref "U3") (pin "9") (pinfunction "IO33/A1_5/X32N_9") (pintype "bidirectional"))
    )
    (net (code "92") (name "ROW_HIGH_DRV_EN") (class "Default")
      (node (ref "R35") (pin "1") (pinfunction "1_1") (pintype "passive"))
      (node (ref "U10") (pin "14") (pinfunction "OUT_EN_14") (pintype "bidirectional"))
      (node (ref "U4") (pin "3") (pinfunction "1Y_3") (pintype "bidirectional"))
      (node (ref "U7") (pin "14") (pinfunction "OUT_EN_14") (pintype "bidirectional"))
    )
    (net (code "93") (name "ROW_HIGH_DRV_EN_CTL") (class "Default")
      (node (ref "Q6") (pin "3") (pinfunction "D_3") (pintype "bidirectional"))
      (node (ref "R18") (pin "1") (pinfunction "1_1") (pintype "passive"))
      (node (ref "U4") (pin "1") (pinfunction "1A_1") (pintype "bidirectional"))
      (node (ref "U4") (pin "5") (pinfunction "2A_5") (pintype "bidirectional"))
    )
    (net (code "94") (name "ROW_HIGH_DRV_EN_CTL_LV") (class "Default")
      (node (ref "Q6") (pin "2") (pinfunction "S_2") (pintype "bidirectional"))
      (node (ref "R14") (pin "1") (pinfunction "1_1") (pintype "passive"))
      (node (ref "U3") (pin "10") (pinfunction "IO25/DAC1/A2_8_10") (pintype "bidirectional"))
    )
    (net (code "95") (name "ROW_LOW_DRV_EN") (class "Default")
      (node (ref "R36") (pin "1") (pinfunction "1_1") (pintype "passive"))
      (node (ref "U4") (pin "10") (pinfunction "3Y_10") (pintype "bidirectional"))
      (node (ref "U6") (pin "8") (pinfunction "OUT_EN_8") (pintype "bidirectional"))
      (node (ref "U9") (pin "8") (pinfunction "OUT_EN_8") (pintype "bidirectional"))
    )
    (net (code "96") (name "ROW_LOW_DRV_EN_CTL") (class "Default")
      (node (ref "Q5") (pin "3") (pinfunction "D_3") (pintype "bidirectional"))
      (node (ref "R17") (pin "1") (pinfunction "1_1") (pintype "passive"))
      (node (ref "U4") (pin "6") (pinfunction "2B_6") (pintype "bidirectional"))
      (node (ref "U4") (pin "9") (pinfunction "3B_9") (pintype "bidirectional"))
    )
    (net (code "97") (name "ROW_LOW_DRV_EN_CTL_LV") (class "Default")
      (node (ref "Q5") (pin "2") (pinfunction "S_2") (pintype "bidirectional"))
      (node (ref "R13") (pin "1") (pinfunction "1_1") (pintype "passive"))
      (node (ref "U3") (pin "11") (pinfunction "IO26/DAC2/A2_9_11") (pintype "bidirectional"))
    )
    (net (code "98") (name "ROW_S_IN") (class "Default")
      (node (ref "Q3") (pin "3") (pinfunction "D_3") (pintype "bidirectional"))
      (node (ref "R15") (pin "1") (pinfunction "1_1") (pintype "passive"))
      (node (ref "U6") (pin "3") (pinfunction "S_IN_3") (pintype "bidirectional"))
      (node (ref "U7") (pin "3") (pinfunction "S_IN_3") (pintype "bidirectional"))
    )
    (net (code "99") (name "ROW_S_IN_LV") (class "Default")
      (node (ref "Q3") (pin "2") (pinfunction "S_2") (pintype "bidirectional"))
      (node (ref "R11") (pin "1") (pinfunction "1_1") (pintype "passive"))
      (node (ref "U3") (pin "8") (pinfunction "IO32/A1_4/X32P_8") (pintype "bidirectional"))
    )
    (net (code "100") (name "RTS") (class "Default")
      (node (ref "Q1") (pin "1") (pinfunction "G_1") (pintype "bidirectional"))
      (node (ref "Q2") (pin "2") (pinfunction "S_2") (pintype "bidirectional"))
      (node (ref "R3") (pin "1") (pinfunction "1_1") (pintype "passive"))
      (node (ref "U2") (pin "2") (pinfunction "RTS_2") (pintype "output"))
    )
    (net (code "101") (name "SIG_SW1") (class "Default")
      (node (ref "J7") (pin "P$1") (pinfunction "1_P$1") (pintype "bidirectional"))
      (node (ref "R21") (pin "1") (pinfunction "1_1") (pintype "passive"))
      (node (ref "U3") (pin "31") (pinfunction "IO19_31") (pintype "bidirectional"))
    )
    (net (code "102") (name "SIG_SW2") (class "Default")
      (node (ref "J7") (pin "P$2") (pinfunction "2_P$2") (pintype "bidirectional"))
      (node (ref "R20") (pin "1") (pinfunction "1_1") (pintype "passive"))
      (node (ref "U3") (pin "33") (pinfunction "IO21_33") (pintype "bidirectional"))
    )
    (net (code "103") (name "SIG_SW3") (class "Default")
      (node (ref "J7") (pin "P$3") (pinfunction "3_P$3") (pintype "bidirectional"))
      (node (ref "R10") (pin "1") (pinfunction "1_1") (pintype "passive"))
      (node (ref "U3") (pin "29") (pinfunction "IO5_29") (pintype "bidirectional"))
    )
    (net (code "104") (name "SIG_SW4") (class "Default")
      (node (ref "J7") (pin "P$4") (pinfunction "4_P$4") (pintype "bidirectional"))
      (node (ref "R8") (pin "1") (pinfunction "1_1") (pintype "passive"))
      (node (ref "U3") (pin "30") (pinfunction "IO18_30") (pintype "bidirectional"))
    )
    (net (code "105") (name "SIG_SW5") (class "Default")
      (node (ref "J7") (pin "P$5") (pinfunction "5_P$5") (pintype "bidirectional"))
      (node (ref "R7") (pin "1") (pinfunction "1_1") (pintype "passive"))
      (node (ref "U3") (pin "27") (pinfunction "IO16/RXD2_27") (pintype "bidirectional"))
    )
    (net (code "106") (name "SIG_SW6") (class "Default")
      (node (ref "J7") (pin "P$6") (pinfunction "6_P$6") (pintype "bidirectional"))
      (node (ref "R6") (pin "1") (pinfunction "1_1") (pintype "passive"))
      (node (ref "U3") (pin "28") (pinfunction "IO17/TXD2_28") (pintype "bidirectional"))
    )
    (net (code "107") (name "VBUS") (class "Default")
      (node (ref "J1") (pin "1") (pinfunction "VBUS_1") (pintype "bidirectional"))
      (node (ref "U2") (pin "15") (pinfunction "VCC_15") (pintype "power_in"))
    )
    (net (code "108") (name "unconnected-(J7-7-PadP$7)") (class "Default")
      (node (ref "J7") (pin "P$7") (pinfunction "7_P$7") (pintype "bidirectional"))
    )
    (net (code "109") (name "unconnected-(J7-8-PadP$8)") (class "Default")
      (node (ref "J7") (pin "P$8") (pinfunction "8_P$8") (pintype "bidirectional"))
    )
    (net (code "110") (name "unconnected-(J7-9-PadP$9)") (class "Default")
      (node (ref "J7") (pin "P$9") (pinfunction "9_P$9") (pintype "bidirectional"))
    )
    (net (code "111") (name "unconnected-(J7-10-PadP$10)") (class "Default")
      (node (ref "J7") (pin "P$10") (pinfunction "10_P$10") (pintype "bidirectional"))
    )
    (net (code "112") (name "unconnected-(J7-11-PadP$11)") (class "Default")
      (node (ref "J7") (pin "P$11") (pinfunction "11_P$11") (pintype "bidirectional"))
    )
    (net (code "113") (name "unconnected-(J7-12-PadP$12)") (class "Default")
      (node (ref "J7") (pin "P$12") (pinfunction "12_P$12") (pintype "bidirectional"))
    )
    (net (code "114") (name "unconnected-(U2-CTS-Pad9)") (class "Default")
      (node (ref "U2") (pin "9") (pinfunction "CTS_9") (pintype "input"))
    )
    (net (code "115") (name "unconnected-(U2-DCD-Pad8)") (class "Default")
      (node (ref "U2") (pin "8") (pinfunction "DCD_8") (pintype "input"))
    )
    (net (code "116") (name "unconnected-(U2-DSR-Pad7)") (class "Default")
      (node (ref "U2") (pin "7") (pinfunction "DSR_7") (pintype "input"))
    )
    (net (code "117") (name "unconnected-(U2-RI-Pad5)") (class "Default")
      (node (ref "U2") (pin "5") (pinfunction "RI_5") (pintype "input"))
    )
    (net (code "118") (name "unconnected-(U2-RXLED-Pad17)") (class "Default")
      (node (ref "U2") (pin "17") (pinfunction "RXLED_17") (pintype "input"))
    )
    (net (code "119") (name "unconnected-(U2-SLEEP-Pad19)") (class "Default")
      (node (ref "U2") (pin "19") (pinfunction "SLEEP_19") (pintype "input"))
    )
    (net (code "120") (name "unconnected-(U2-TXDEN-Pad18)") (class "Default")
      (node (ref "U2") (pin "18") (pinfunction "TXDEN_18") (pintype "input"))
    )
    (net (code "121") (name "unconnected-(U2-TXLED-Pad10)") (class "Default")
      (node (ref "U2") (pin "10") (pinfunction "TXLED_10") (pintype "input"))
    )
    (net (code "122") (name "unconnected-(U3-I34{slash}A1_6-Pad6)") (class "Default")
      (node (ref "U3") (pin "6") (pinfunction "I34/A1_6_6") (pintype "input"))
    )
    (net (code "123") (name "unconnected-(U3-I35{slash}A1_7-Pad7)") (class "Default")
      (node (ref "U3") (pin "7") (pinfunction "I35/A1_7_7") (pintype "input"))
    )
    (net (code "124") (name "unconnected-(U3-I36{slash}SEN_VP{slash}A1_0-Pad4)") (class "Default")
      (node (ref "U3") (pin "4") (pinfunction "I36/SEN_VP/A1_0_4") (pintype "input"))
    )
    (net (code "125") (name "unconnected-(U3-I39{slash}SEN_VN{slash}A1_3-Pad5)") (class "Default")
      (node (ref "U3") (pin "5") (pinfunction "I39/SEN_VN/A1_3_5") (pintype "input"))
    )
    (net (code "126") (name "unconnected-(U3-IO2{slash}A2_2-Pad24)") (class "Default")
      (node (ref "U3") (pin "24") (pinfunction "IO2/A2_2_24") (pintype "bidirectional"))
    )
    (net (code "127") (name "unconnected-(U3-IO4{slash}A2_0-Pad26)") (class "Default")
      (node (ref "U3") (pin "26") (pinfunction "IO4/A2_0_26") (pintype "bidirectional"))
    )
    (net (code "128") (name "unconnected-(U3-IO12{slash}A2_5-Pad14)") (class "Default")
      (node (ref "U3") (pin "14") (pinfunction "IO12/A2_5_14") (pintype "bidirectional"))
    )
    (net (code "129") (name "unconnected-(U3-IO13{slash}A2_4-Pad16)") (class "Default")
      (node (ref "U3") (pin "16") (pinfunction "IO13/A2_4_16") (pintype "bidirectional"))
    )
    (net (code "130") (name "unconnected-(U3-IO15{slash}A2_3-Pad23)") (class "Default")
      (node (ref "U3") (pin "23") (pinfunction "IO15/A2_3_23") (pintype "bidirectional"))
    )
    (net (code "131") (name "unconnected-(U4-4Y-Pad11)") (class "Default")
      (node (ref "U4") (pin "11") (pinfunction "4Y_11") (pintype "bidirectional"))
    )
    (net (code "132") (name "unconnected-(U9-OUT7-Pad12)") (class "Default")
      (node (ref "U9") (pin "12") (pinfunction "OUT7_12") (pintype "bidirectional"))
    )
    (net (code "133") (name "unconnected-(U9-OUT8-Pad11)") (class "Default")
      (node (ref "U9") (pin "11") (pinfunction "OUT8_11") (pintype "bidirectional"))
    )
    (net (code "134") (name "unconnected-(U9-S_OUT-Pad6)") (class "Default")
      (node (ref "U9") (pin "6") (pinfunction "S_OUT_6") (pintype "bidirectional"))
    )
    (net (code "135") (name "unconnected-(U10-OUT7-Pad11)") (class "Default")
      (node (ref "U10") (pin "11") (pinfunction "OUT7_11") (pintype "bidirectional"))
    )
    (net (code "136") (name "unconnected-(U10-OUT8-Pad12)") (class "Default")
      (node (ref "U10") (pin "12") (pinfunction "OUT8_12") (pintype "bidirectional"))
    )
    (net (code "137") (name "unconnected-(U10-S_OUT-Pad16)") (class "Default")
      (node (ref "U10") (pin "16") (pinfunction "S_OUT_16") (pintype "bidirectional"))
    )
    (net (code "138") (name "unconnected-(U11-OUT8-Pad11)") (class "Default")
      (node (ref "U11") (pin "11") (pinfunction "OUT8_11") (pintype "bidirectional"))
    )
    (net (code "139") (name "unconnected-(U12-OUT8-Pad11)") (class "Default")
      (node (ref "U12") (pin "11") (pinfunction "OUT8_11") (pintype "bidirectional"))
    )
    (net (code "140") (name "unconnected-(U13-OUT8-Pad12)") (class "Default")
      (node (ref "U13") (pin "12") (pinfunction "OUT8_12") (pintype "bidirectional"))
    )
    (net (code "141") (name "unconnected-(U14-OUT8-Pad12)") (class "Default")
      (node (ref "U14") (pin "12") (pinfunction "OUT8_12") (pintype "bidirectional"))
    )
    (net (code "142") (name "unconnected-(U15-4Y-Pad11)") (class "Default")
      (node (ref "U15") (pin "11") (pinfunction "4Y_11") (pintype "bidirectional"))
    )
    (net (code "143") (name "unconnected-(U16-OUT8-Pad11)") (class "Default")
      (node (ref "U16") (pin "11") (pinfunction "OUT8_11") (pintype "bidirectional"))
    )
    (net (code "144") (name "unconnected-(U16-S_OUT-Pad6)") (class "Default")
      (node (ref "U16") (pin "6") (pinfunction "S_OUT_6") (pintype "bidirectional"))
    )
    (net (code "145") (name "unconnected-(U17-OUT8-Pad12)") (class "Default")
      (node (ref "U17") (pin "12") (pinfunction "OUT8_12") (pintype "bidirectional"))
    )
    (net (code "146") (name "unconnected-(U17-S_OUT-Pad16)") (class "Default")
      (node (ref "U17") (pin "16") (pinfunction "S_OUT_16") (pintype "bidirectional"))
    )
  )
)
